# power_supplies.net
KiCad netlist of a schematic drawn in Altium Designer
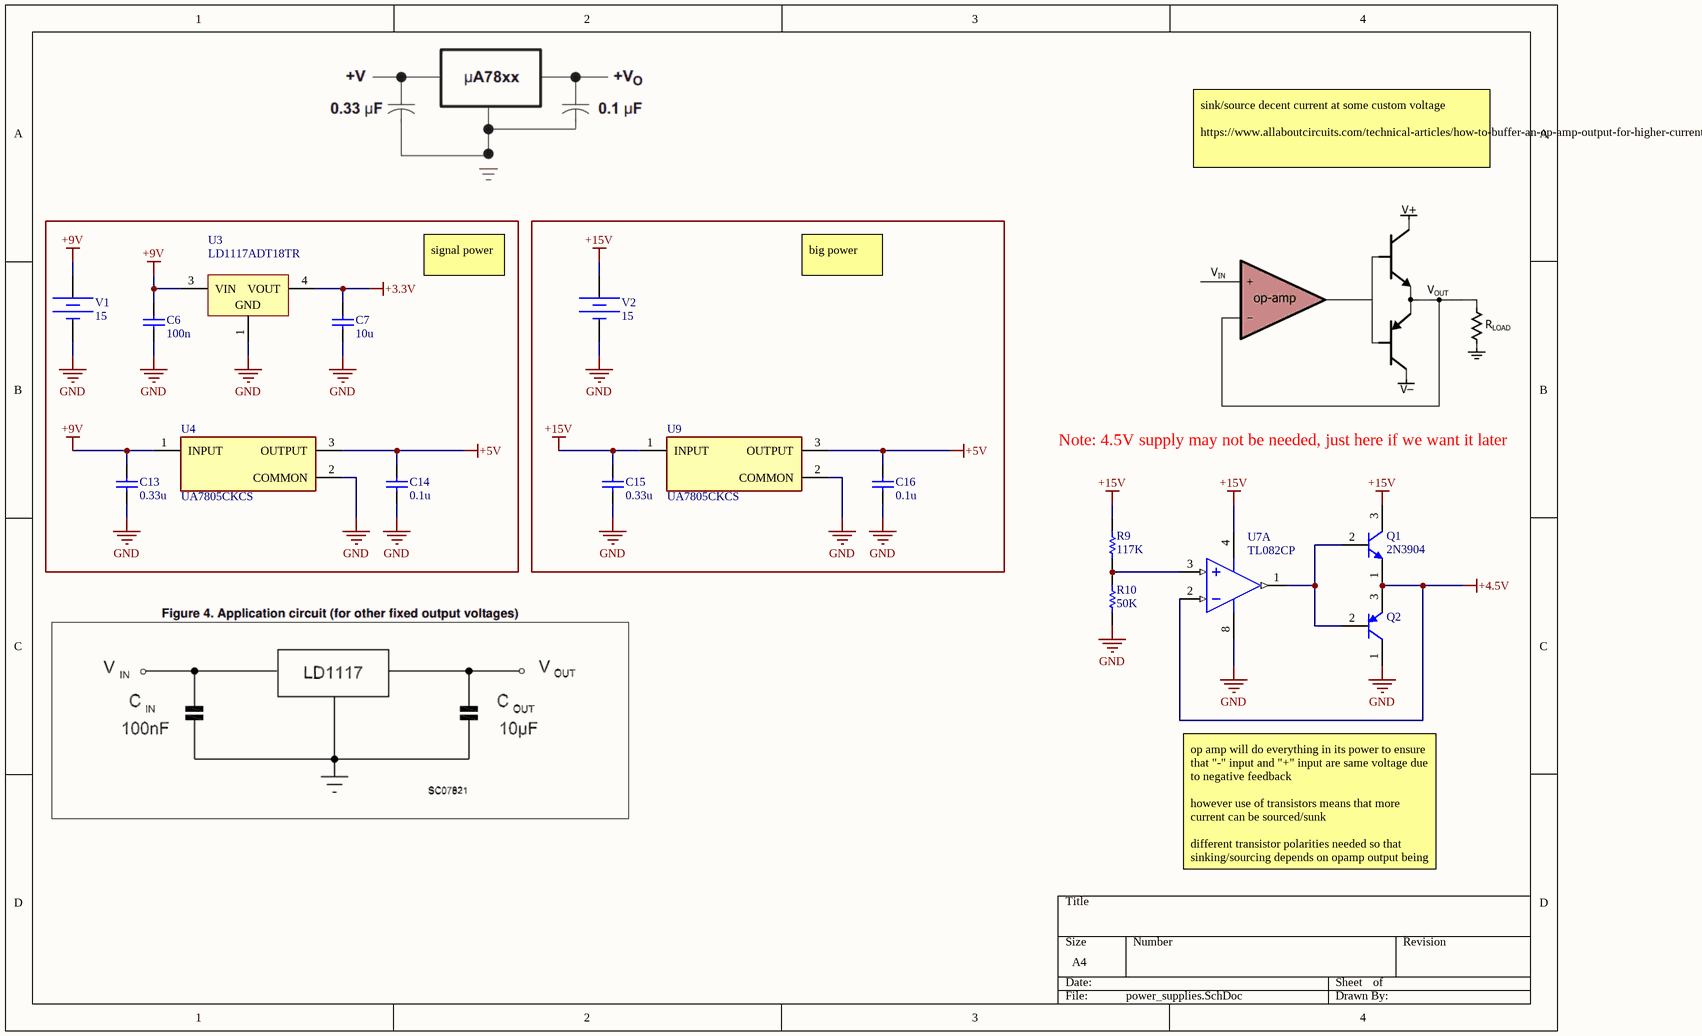
[diagram p0: power_supplies.SchDoc]

(export (version "E")
  (design (tool "Eeschema 10.0.6"))
  (components
    (comp (ref "C6")
      (value "100n")
      (description "Capacitor")
      (libsource (lib "Simulation Generic Components") (part "Capacitor"))
    )
    (comp (ref "C7")
      (value "10u")
      (description "Capacitor")
      (libsource (lib "Simulation Generic Components") (part "Capacitor"))
    )
    (comp (ref "C13")
      (value "0.33u")
      (description "Capacitor")
      (libsource (lib "Simulation Generic Components") (part "Capacitor"))
    )
    (comp (ref "C14")
      (value "0.1u")
      (description "Capacitor")
      (libsource (lib "Simulation Generic Components") (part "Capacitor"))
    )
    (comp (ref "C15")
      (value "0.33u")
      (description "Capacitor")
      (libsource (lib "Simulation Generic Components") (part "Capacitor"))
    )
    (comp (ref "C16")
      (value "0.1u")
      (description "Capacitor")
      (libsource (lib "Simulation Generic Components") (part "Capacitor"))
    )
    (comp (ref "Q1")
      (value "2N3904")
      (footprint "ONSC-TO-92-3-29-11")
      (description "General Purpose Transistor, NPN Silicon, 200 mA, 60 V, -55 to 150 degC, 3-Pin TO-92, RoHS, Bulk")
      (fields (field (name "MANUFACTURER") "ONSemiconductor"))
      (libsource (lib "Altium Content Vault") (part "BJT-NPN-EBC-3"))
    )
    (comp (ref "Q2")
      (value "BC327-40ZL1G")
      (footprint "ONSC-TO-92-3-29-11_AM_BL")
      (description "Amplifier Transistor, PNP Silicon, 3-Pin TO-92, Pb-Free, Ammo Box")
      (fields (field (name "MANUFACTURER") "On Semiconductor"))
      (libsource (lib "Altium Content Vault") (part "ONSC-PNP-C1B2E3-3"))
    )
    (comp (ref "R9")
      (value "117K")
      (description "Resistor")
      (libsource (lib "Simulation Generic Components") (part "Resistor"))
    )
    (comp (ref "R10")
      (value "50K")
      (description "Resistor")
      (libsource (lib "Simulation Generic Components") (part "Resistor"))
    )
    (comp (ref "U3")
      (value "LD1117ADT18TR")
      (footprint "TO-252_N")
      (description "1A, Low Drop Positive Voltage Regulator, 1.8V, 3-Pin DPAK, Tape and Reel")
      (libsource (lib "Altium Content Vault") (part "PM-REG-LD1117-SOT3"))
    )
    (comp (ref "U4")
      (value "UA7805CKCS")
      (footprint "FP-KCS0003B-MFG")
      (description "IC REG LINEAR 5V 1.5A TO220-3")
      (fields
        (field (name "MANUFACTURER") "Texas Instruments")
        (field (name "OCTOPART") "https://octopart.com/ua7805ckcs-texas+instruments-525328")
      )
      (libsource (lib "Altium Content Vault") (part "39cda3df25f6f2ed05b52b08d4ba2c1"))
    )
    (comp (ref "U7")
      (value "TL082CP")
      (footprint "P0008A")
      (description "JFET-Input Operational Amplifier, 7 to 36 V, 0 to 70 degC, 8-pin DIP (P8), Pb-Free (RoHS)")
      (fields (field (name "MANUFACTURER") "Texas Instruments"))
      (libsource (lib "Altium Content Vault") (part "TI-AMP-D6-2-8_D"))
    )
    (comp (ref "U9")
      (value "UA7805CKCS")
      (footprint "FP-KCS0003B-MFG")
      (description "IC REG LINEAR 5V 1.5A TO220-3")
      (fields
        (field (name "MANUFACTURER") "Texas Instruments")
        (field (name "OCTOPART") "https://octopart.com/ua7805ckcs-texas+instruments-525328")
      )
      (libsource (lib "Altium Content Vault") (part "39cda3df25f6f2ed05b52b08d4ba2c1"))
    )
    (comp (ref "V1")
      (value "Constant Voltage Source")
      (fields (field (name "DC MAGNITUDE") "15"))
      (libsource (lib "Simulation Generic Components") (part "Battery"))
    )
    (comp (ref "V2")
      (value "Constant Voltage Source")
      (fields (field (name "DC MAGNITUDE") "15"))
      (libsource (lib "Simulation Generic Components") (part "Battery"))
    )
  )
  (nets
    (net (code "1") (name "+3.3V") (class "Default")
      (node (ref "C7") (pin "1") (pinfunction "1_1") (pintype "passive"))
      (node (ref "U3") (pin "4") (pinfunction "VOUT_4") (pintype "power_in"))
    )
    (net (code "2") (name "+4.5V") (class "Default")
      (node (ref "Q1") (pin "1") (pinfunction "E_1") (pintype "passive"))
      (node (ref "Q2") (pin "3") (pinfunction "E_3") (pintype "passive"))
      (node (ref "U7") (pin "2") (pinfunction "IN1-_2") (pintype "input"))
    )
    (net (code "3") (name "+5V") (class "Default")
      (node (ref "C14") (pin "1") (pinfunction "1_1") (pintype "passive"))
      (node (ref "C16") (pin "1") (pinfunction "1_1") (pintype "passive"))
      (node (ref "U4") (pin "3") (pinfunction "OUTPUT_3") (pintype "power_in"))
      (node (ref "U9") (pin "3") (pinfunction "OUTPUT_3") (pintype "power_in"))
    )
    (net (code "4") (name "+9V") (class "Default")
      (node (ref "C13") (pin "1") (pinfunction "1_1") (pintype "passive"))
      (node (ref "C6") (pin "1") (pinfunction "1_1") (pintype "passive"))
      (node (ref "U3") (pin "3") (pinfunction "VIN_3") (pintype "power_in"))
      (node (ref "U4") (pin "1") (pinfunction "INPUT_1") (pintype "power_in"))
      (node (ref "V1") (pin "1") (pinfunction "1_1") (pintype "passive"))
    )
    (net (code "5") (name "+15V") (class "Default")
      (node (ref "C15") (pin "1") (pinfunction "1_1") (pintype "passive"))
      (node (ref "Q1") (pin "3") (pinfunction "C_3") (pintype "passive"))
      (node (ref "R9") (pin "1") (pinfunction "1_1") (pintype "passive"))
      (node (ref "U7") (pin "4") (pinfunction "VCC-_4") (pintype "power_in"))
      (node (ref "U9") (pin "1") (pinfunction "INPUT_1") (pintype "power_in"))
      (node (ref "V2") (pin "1") (pinfunction "1_1") (pintype "passive"))
    )
    (net (code "6") (name "GND") (class "Default")
      (node (ref "C13") (pin "2") (pinfunction "2_2") (pintype "passive"))
      (node (ref "C14") (pin "2") (pinfunction "2_2") (pintype "passive"))
      (node (ref "C15") (pin "2") (pinfunction "2_2") (pintype "passive"))
      (node (ref "C16") (pin "2") (pinfunction "2_2") (pintype "passive"))
      (node (ref "C6") (pin "2") (pinfunction "2_2") (pintype "passive"))
      (node (ref "C7") (pin "2") (pinfunction "2_2") (pintype "passive"))
      (node (ref "Q2") (pin "1") (pinfunction "C_1") (pintype "passive"))
      (node (ref "R10") (pin "2") (pinfunction "2_2") (pintype "passive"))
      (node (ref "U3") (pin "1") (pinfunction "GND_1") (pintype "power_in"))
      (node (ref "U4") (pin "2") (pinfunction "COMMON_2") (pintype "power_in"))
      (node (ref "U7") (pin "8") (pinfunction "VCC+_8") (pintype "power_in"))
      (node (ref "U9") (pin "2") (pinfunction "COMMON_2") (pintype "power_in"))
      (node (ref "V1") (pin "2") (pinfunction "2_2") (pintype "passive"))
      (node (ref "V2") (pin "2") (pinfunction "2_2") (pintype "passive"))
    )
    (net (code "7") (name "Net-(Q1-B)") (class "Default")
      (node (ref "Q1") (pin "2") (pinfunction "B_2") (pintype "passive"))
      (node (ref "Q2") (pin "2") (pinfunction "B_2") (pintype "passive"))
      (node (ref "U7") (pin "1") (pinfunction "OUT1_1") (pintype "output"))
    )
    (net (code "8") (name "Net-(U7A-IN1+)") (class "Default")
      (node (ref "R10") (pin "1") (pinfunction "1_1") (pintype "passive"))
      (node (ref "R9") (pin "2") (pinfunction "2_2") (pintype "passive"))
      (node (ref "U7") (pin "3") (pinfunction "IN1+_3") (pintype "input"))
    )
  )
)
